# 1-Schematic_WIFI_WAVER.net
KiCad netlist of a schematic drawn in EasyEDA
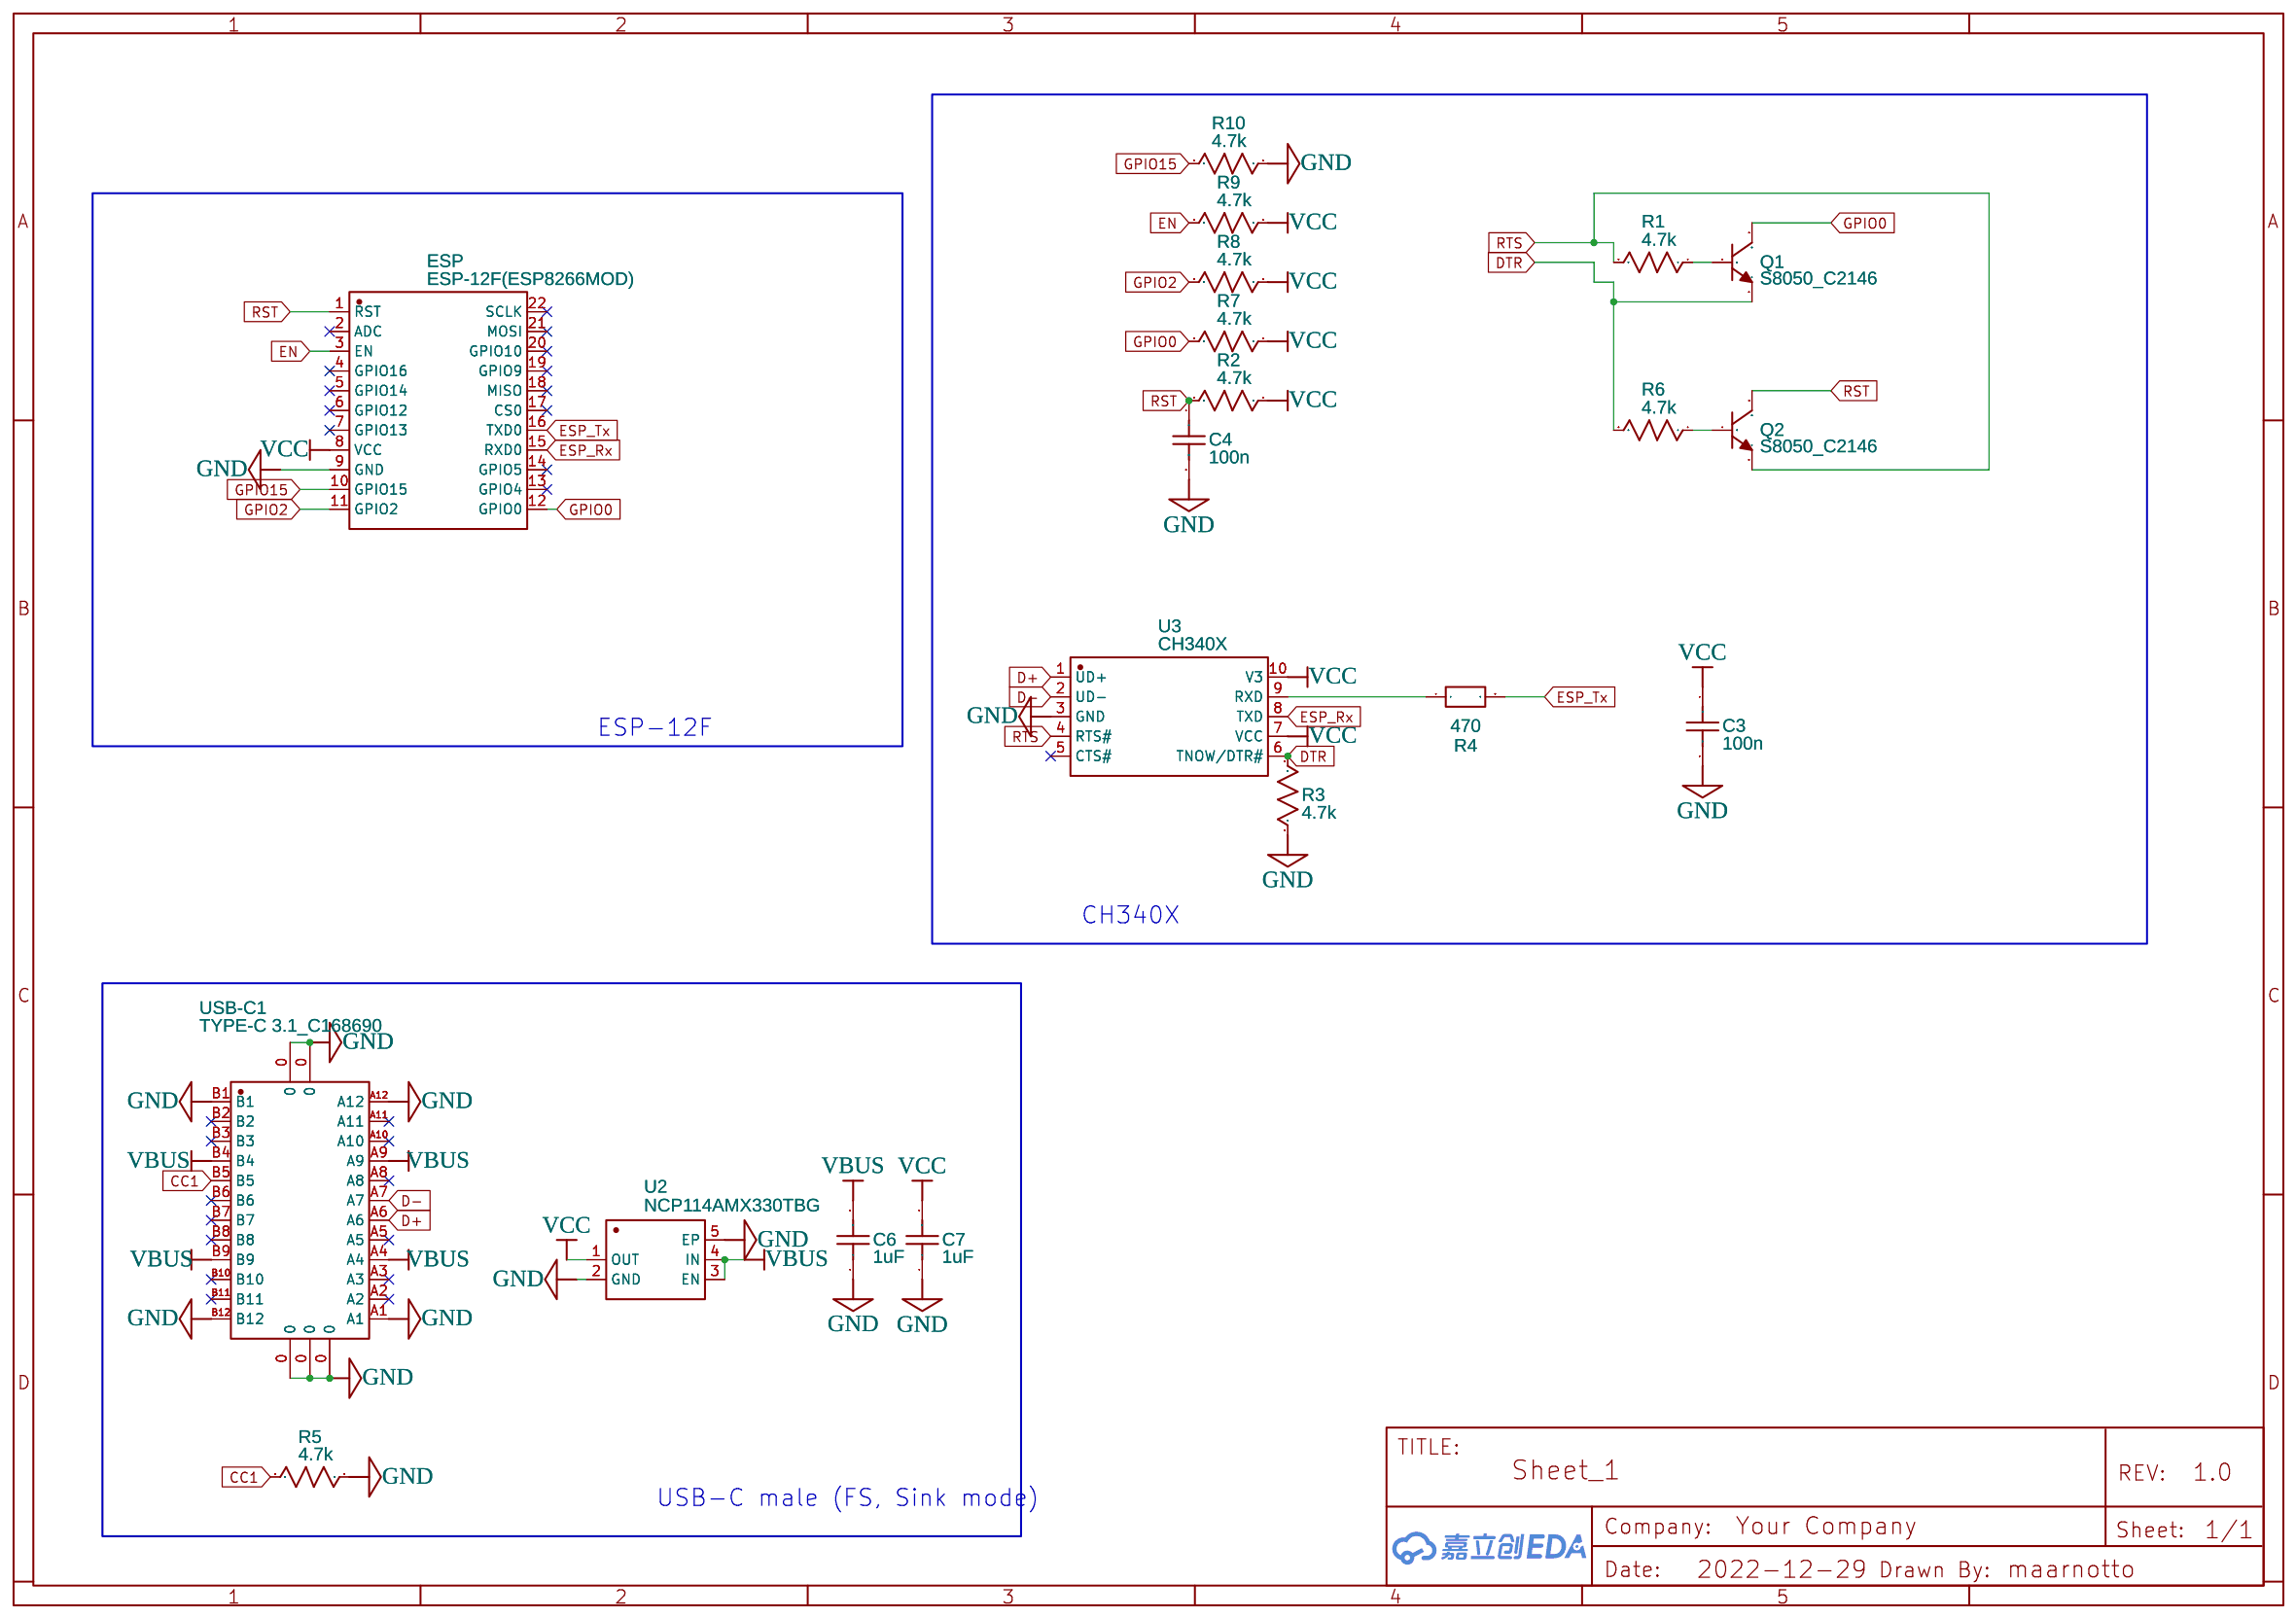
[diagram p0: schematic sheet]

(export (version "E")
  (design (tool "Eeschema 10.0.6"))
  (components
    (comp (ref "C3") (value "100n") (libsource (lib "") (part "C_0603_US_1")))
    (comp (ref "C4") (value "100n") (libsource (lib "") (part "C_0603_US_1")))
    (comp (ref "C6") (value "1uF") (libsource (lib "") (part "C_0603_US")))
    (comp (ref "C7") (value "1uF") (libsource (lib "") (part "C_0603_US")))
    (comp (ref "ESP")
      (value "ESP-12F(ESP8266MOD)")
      (fields (field (name "Manufacturer") "Ai-Thinker(安信可)"))
      (libsource (lib "") (part "ESP-12F(ESP8266MOD)"))
    )
    (comp (ref "Q1")
      (value "S8050_C2146")
      (fields (field (name "Manufacturer Part") "S8050 J3Y") (field (name "Manufacturer") "CJ(江苏长电/长晶)"))
      (libsource (lib "") (part "S8050_C2146"))
    )
    (comp (ref "Q2")
      (value "S8050_C2146")
      (fields (field (name "Manufacturer Part") "S8050 J3Y") (field (name "Manufacturer") "CJ(江苏长电/长晶)"))
      (libsource (lib "") (part "S8050_C2146"))
    )
    (comp (ref "R1") (value "4.7k") (libsource (lib "") (part "R_0603_US")))
    (comp (ref "R2") (value "4.7k") (libsource (lib "") (part "R_0603_US")))
    (comp (ref "R3") (value "4.7k") (libsource (lib "") (part "R_0603_US_1")))
    (comp (ref "R4") (value "470") (libsource (lib "") (part "R_0603_EU")))
    (comp (ref "R5") (value "4.7k") (libsource (lib "") (part "R_0603_US")))
    (comp (ref "R6") (value "4.7k") (libsource (lib "") (part "R_0603_US")))
    (comp (ref "R7") (value "4.7k") (libsource (lib "") (part "R_0603_US")))
    (comp (ref "R8") (value "4.7k") (libsource (lib "") (part "R_0603_US")))
    (comp (ref "R9") (value "4.7k") (libsource (lib "") (part "R_0603_US")))
    (comp (ref "R10") (value "4.7k") (libsource (lib "") (part "R_0603_US")))
    (comp (ref "U2")
      (value "NCP114AMX330TBG")
      (fields (field (name "Manufacturer") "onsemi(安森美)"))
      (libsource (lib "") (part "NCP114AMX330TBG"))
    )
    (comp (ref "U3")
      (value "CH340X")
      (fields (field (name "Manufacturer") "WCH(南京沁恒)"))
      (libsource (lib "") (part "CH340X"))
    )
    (comp (ref "USB-C1")
      (value "TYPE-C 3.1_C168690")
      (fields (field (name "Manufacturer Part") "918-118A2021Y40000") (field (name "Manufacturer") "精拓金"))
      (libsource (lib "") (part "TYPE-C 3.1_C168690"))
    )
  )
  (nets
    (net (code "1") (name "CC1") (class "Default")
      (node (ref "R5") (pin "2") (pinfunction "2_2") (pintype "unspecified"))
      (node (ref "USB-C1") (pin "B5") (pinfunction "B5_B5") (pintype "unspecified"))
    )
    (net (code "2") (name "D+") (class "Default")
      (node (ref "U3") (pin "1") (pinfunction "UD+_1") (pintype "unspecified"))
      (node (ref "USB-C1") (pin "A6") (pinfunction "A6_A6") (pintype "unspecified"))
    )
    (net (code "3") (name "D-") (class "Default")
      (node (ref "U3") (pin "2") (pinfunction "UD-_2") (pintype "unspecified"))
      (node (ref "USB-C1") (pin "A7") (pinfunction "A7_A7") (pintype "unspecified"))
    )
    (net (code "4") (name "DTR") (class "Default")
      (node (ref "Q1") (pin "2") (pinfunction "E_2") (pintype "unspecified"))
      (node (ref "R3") (pin "2") (pinfunction "2_2") (pintype "unspecified"))
      (node (ref "R6") (pin "2") (pinfunction "2_2") (pintype "unspecified"))
      (node (ref "U3") (pin "6") (pinfunction "TNOW/DTR#_6") (pintype "unspecified"))
    )
    (net (code "5") (name "EN") (class "Default")
      (node (ref "ESP") (pin "3") (pinfunction "EN_3") (pintype "unspecified"))
      (node (ref "R9") (pin "2") (pinfunction "2_2") (pintype "unspecified"))
    )
    (net (code "6") (name "ESP_Rx") (class "Default")
      (node (ref "ESP") (pin "15") (pinfunction "RXD0_15") (pintype "unspecified"))
      (node (ref "U3") (pin "8") (pinfunction "TXD_8") (pintype "unspecified"))
    )
    (net (code "7") (name "ESP_Tx") (class "Default")
      (node (ref "ESP") (pin "16") (pinfunction "TXD0_16") (pintype "unspecified"))
      (node (ref "R4") (pin "2") (pinfunction "2_2") (pintype "unspecified"))
    )
    (net (code "8") (name "GND") (class "Default")
      (node (ref "C3") (pin "2") (pinfunction "2_2") (pintype "unspecified"))
      (node (ref "C4") (pin "2") (pinfunction "2_2") (pintype "unspecified"))
      (node (ref "C6") (pin "1") (pinfunction "1_1") (pintype "unspecified"))
      (node (ref "C7") (pin "1") (pinfunction "1_1") (pintype "unspecified"))
      (node (ref "ESP") (pin "9") (pinfunction "GND_9") (pintype "unspecified"))
      (node (ref "R10") (pin "1") (pinfunction "1_1") (pintype "unspecified"))
      (node (ref "R3") (pin "1") (pinfunction "1_1") (pintype "unspecified"))
      (node (ref "R5") (pin "1") (pinfunction "1_1") (pintype "unspecified"))
      (node (ref "U2") (pin "2") (pinfunction "GND_2") (pintype "unspecified"))
      (node (ref "U2") (pin "5") (pinfunction "EP_5") (pintype "unspecified"))
      (node (ref "U3") (pin "3") (pinfunction "GND_3") (pintype "unspecified"))
      (node (ref "USB-C1") (pin "0") (pinfunction "0_0") (pintype "unspecified"))
      (node (ref "USB-C1") (pin "A1") (pinfunction "A1_A1") (pintype "unspecified"))
      (node (ref "USB-C1") (pin "A12") (pinfunction "A12_A12") (pintype "unspecified"))
      (node (ref "USB-C1") (pin "B1") (pinfunction "B1_B1") (pintype "unspecified"))
      (node (ref "USB-C1") (pin "B12") (pinfunction "B12_B12") (pintype "unspecified"))
    )
    (net (code "9") (name "GPIO0") (class "Default")
      (node (ref "ESP") (pin "12") (pinfunction "GPIO0_12") (pintype "unspecified"))
      (node (ref "Q1") (pin "3") (pinfunction "C_3") (pintype "unspecified"))
      (node (ref "R7") (pin "2") (pinfunction "2_2") (pintype "unspecified"))
    )
    (net (code "10") (name "GPIO2") (class "Default")
      (node (ref "ESP") (pin "11") (pinfunction "GPIO2_11") (pintype "unspecified"))
      (node (ref "R8") (pin "2") (pinfunction "2_2") (pintype "unspecified"))
    )
    (net (code "11") (name "GPIO15") (class "Default")
      (node (ref "ESP") (pin "10") (pinfunction "GPIO15_10") (pintype "unspecified"))
      (node (ref "R10") (pin "2") (pinfunction "2_2") (pintype "unspecified"))
    )
    (net (code "12") (name "Net-(Q1-B)") (class "Default")
      (node (ref "Q1") (pin "1") (pinfunction "B_1") (pintype "unspecified"))
      (node (ref "R1") (pin "1") (pinfunction "1_1") (pintype "unspecified"))
    )
    (net (code "13") (name "Net-(Q2-B)") (class "Default")
      (node (ref "Q2") (pin "1") (pinfunction "B_1") (pintype "unspecified"))
      (node (ref "R6") (pin "1") (pinfunction "1_1") (pintype "unspecified"))
    )
    (net (code "14") (name "Net-(U3-RXD)") (class "Default")
      (node (ref "R4") (pin "1") (pinfunction "1_1") (pintype "unspecified"))
      (node (ref "U3") (pin "9") (pinfunction "RXD_9") (pintype "unspecified"))
    )
    (net (code "15") (name "RST") (class "Default")
      (node (ref "C4") (pin "1") (pinfunction "1_1") (pintype "unspecified"))
      (node (ref "ESP") (pin "1") (pinfunction "RST_1") (pintype "unspecified"))
      (node (ref "Q2") (pin "3") (pinfunction "C_3") (pintype "unspecified"))
      (node (ref "R2") (pin "2") (pinfunction "2_2") (pintype "unspecified"))
    )
    (net (code "16") (name "RTS") (class "Default")
      (node (ref "Q2") (pin "2") (pinfunction "E_2") (pintype "unspecified"))
      (node (ref "R1") (pin "2") (pinfunction "2_2") (pintype "unspecified"))
      (node (ref "U3") (pin "4") (pinfunction "RTS#_4") (pintype "unspecified"))
    )
    (net (code "17") (name "VBUS") (class "Default")
      (node (ref "C6") (pin "2") (pinfunction "2_2") (pintype "unspecified"))
      (node (ref "U2") (pin "3") (pinfunction "EN_3") (pintype "unspecified"))
      (node (ref "U2") (pin "4") (pinfunction "IN_4") (pintype "unspecified"))
      (node (ref "USB-C1") (pin "A4") (pinfunction "A4_A4") (pintype "unspecified"))
      (node (ref "USB-C1") (pin "A9") (pinfunction "A9_A9") (pintype "unspecified"))
      (node (ref "USB-C1") (pin "B4") (pinfunction "B4_B4") (pintype "unspecified"))
      (node (ref "USB-C1") (pin "B9") (pinfunction "B9_B9") (pintype "unspecified"))
    )
    (net (code "18") (name "VCC") (class "Default")
      (node (ref "C3") (pin "1") (pinfunction "1_1") (pintype "unspecified"))
      (node (ref "C7") (pin "2") (pinfunction "2_2") (pintype "unspecified"))
      (node (ref "ESP") (pin "8") (pinfunction "VCC_8") (pintype "unspecified"))
      (node (ref "R2") (pin "1") (pinfunction "1_1") (pintype "unspecified"))
      (node (ref "R7") (pin "1") (pinfunction "1_1") (pintype "unspecified"))
      (node (ref "R8") (pin "1") (pinfunction "1_1") (pintype "unspecified"))
      (node (ref "R9") (pin "1") (pinfunction "1_1") (pintype "unspecified"))
      (node (ref "U2") (pin "1") (pinfunction "OUT_1") (pintype "unspecified"))
      (node (ref "U3") (pin "10") (pinfunction "V3_10") (pintype "unspecified"))
      (node (ref "U3") (pin "7") (pinfunction "VCC_7") (pintype "unspecified"))
    )
    (net (code "19") (name "unconnected-(ESP-ADC-Pad2)") (class "Default")
      (node (ref "ESP") (pin "2") (pinfunction "ADC_2") (pintype "unspecified+no_connect"))
    )
    (net (code "20") (name "unconnected-(ESP-CS0-Pad17)") (class "Default")
      (node (ref "ESP") (pin "17") (pinfunction "CS0_17") (pintype "unspecified+no_connect"))
    )
    (net (code "21") (name "unconnected-(ESP-GPIO4-Pad13)") (class "Default")
      (node (ref "ESP") (pin "13") (pinfunction "GPIO4_13") (pintype "unspecified+no_connect"))
    )
    (net (code "22") (name "unconnected-(ESP-GPIO5-Pad14)") (class "Default")
      (node (ref "ESP") (pin "14") (pinfunction "GPIO5_14") (pintype "unspecified+no_connect"))
    )
    (net (code "23") (name "unconnected-(ESP-GPIO9-Pad19)") (class "Default")
      (node (ref "ESP") (pin "19") (pinfunction "GPIO9_19") (pintype "unspecified+no_connect"))
    )
    (net (code "24") (name "unconnected-(ESP-GPIO10-Pad20)") (class "Default")
      (node (ref "ESP") (pin "20") (pinfunction "GPIO10_20") (pintype "unspecified+no_connect"))
    )
    (net (code "25") (name "unconnected-(ESP-GPIO12-Pad6)") (class "Default")
      (node (ref "ESP") (pin "6") (pinfunction "GPIO12_6") (pintype "unspecified+no_connect"))
    )
    (net (code "26") (name "unconnected-(ESP-GPIO13-Pad7)") (class "Default")
      (node (ref "ESP") (pin "7") (pinfunction "GPIO13_7") (pintype "unspecified+no_connect"))
    )
    (net (code "27") (name "unconnected-(ESP-GPIO14-Pad5)") (class "Default")
      (node (ref "ESP") (pin "5") (pinfunction "GPIO14_5") (pintype "unspecified+no_connect"))
    )
    (net (code "28") (name "unconnected-(ESP-GPIO16-Pad4)") (class "Default")
      (node (ref "ESP") (pin "4") (pinfunction "GPIO16_4") (pintype "unspecified+no_connect"))
    )
    (net (code "29") (name "unconnected-(ESP-MISO-Pad18)") (class "Default")
      (node (ref "ESP") (pin "18") (pinfunction "MISO_18") (pintype "unspecified+no_connect"))
    )
    (net (code "30") (name "unconnected-(ESP-MOSI-Pad21)") (class "Default")
      (node (ref "ESP") (pin "21") (pinfunction "MOSI_21") (pintype "unspecified+no_connect"))
    )
    (net (code "31") (name "unconnected-(ESP-SCLK-Pad22)") (class "Default")
      (node (ref "ESP") (pin "22") (pinfunction "SCLK_22") (pintype "unspecified+no_connect"))
    )
    (net (code "32") (name "unconnected-(U3-CTS#-Pad5)") (class "Default")
      (node (ref "U3") (pin "5") (pinfunction "CTS#_5") (pintype "unspecified+no_connect"))
    )
    (net (code "33") (name "unconnected-(USB-C1-PadA2)") (class "Default")
      (node (ref "USB-C1") (pin "A2") (pinfunction "A2_A2") (pintype "unspecified+no_connect"))
    )
    (net (code "34") (name "unconnected-(USB-C1-PadA3)") (class "Default")
      (node (ref "USB-C1") (pin "A3") (pinfunction "A3_A3") (pintype "unspecified+no_connect"))
    )
    (net (code "35") (name "unconnected-(USB-C1-PadA5)") (class "Default")
      (node (ref "USB-C1") (pin "A5") (pinfunction "A5_A5") (pintype "unspecified+no_connect"))
    )
    (net (code "36") (name "unconnected-(USB-C1-PadA8)") (class "Default")
      (node (ref "USB-C1") (pin "A8") (pinfunction "A8_A8") (pintype "unspecified+no_connect"))
    )
    (net (code "37") (name "unconnected-(USB-C1-PadA10)") (class "Default")
      (node (ref "USB-C1") (pin "A10") (pinfunction "A10_A10") (pintype "unspecified+no_connect"))
    )
    (net (code "38") (name "unconnected-(USB-C1-PadA11)") (class "Default")
      (node (ref "USB-C1") (pin "A11") (pinfunction "A11_A11") (pintype "unspecified+no_connect"))
    )
    (net (code "39") (name "unconnected-(USB-C1-PadB2)") (class "Default")
      (node (ref "USB-C1") (pin "B2") (pinfunction "B2_B2") (pintype "unspecified+no_connect"))
    )
    (net (code "40") (name "unconnected-(USB-C1-PadB3)") (class "Default")
      (node (ref "USB-C1") (pin "B3") (pinfunction "B3_B3") (pintype "unspecified+no_connect"))
    )
    (net (code "41") (name "unconnected-(USB-C1-PadB6)") (class "Default")
      (node (ref "USB-C1") (pin "B6") (pinfunction "B6_B6") (pintype "unspecified+no_connect"))
    )
    (net (code "42") (name "unconnected-(USB-C1-PadB7)") (class "Default")
      (node (ref "USB-C1") (pin "B7") (pinfunction "B7_B7") (pintype "unspecified+no_connect"))
    )
    (net (code "43") (name "unconnected-(USB-C1-PadB8)") (class "Default")
      (node (ref "USB-C1") (pin "B8") (pinfunction "B8_B8") (pintype "unspecified+no_connect"))
    )
    (net (code "44") (name "unconnected-(USB-C1-PadB10)") (class "Default")
      (node (ref "USB-C1") (pin "B10") (pinfunction "B10_B10") (pintype "unspecified+no_connect"))
    )
    (net (code "45") (name "unconnected-(USB-C1-PadB11)") (class "Default")
      (node (ref "USB-C1") (pin "B11") (pinfunction "B11_B11") (pintype "unspecified+no_connect"))
    )
  )
)
